# BlueESC.net
KiCad netlist of a schematic drawn in EAGLE
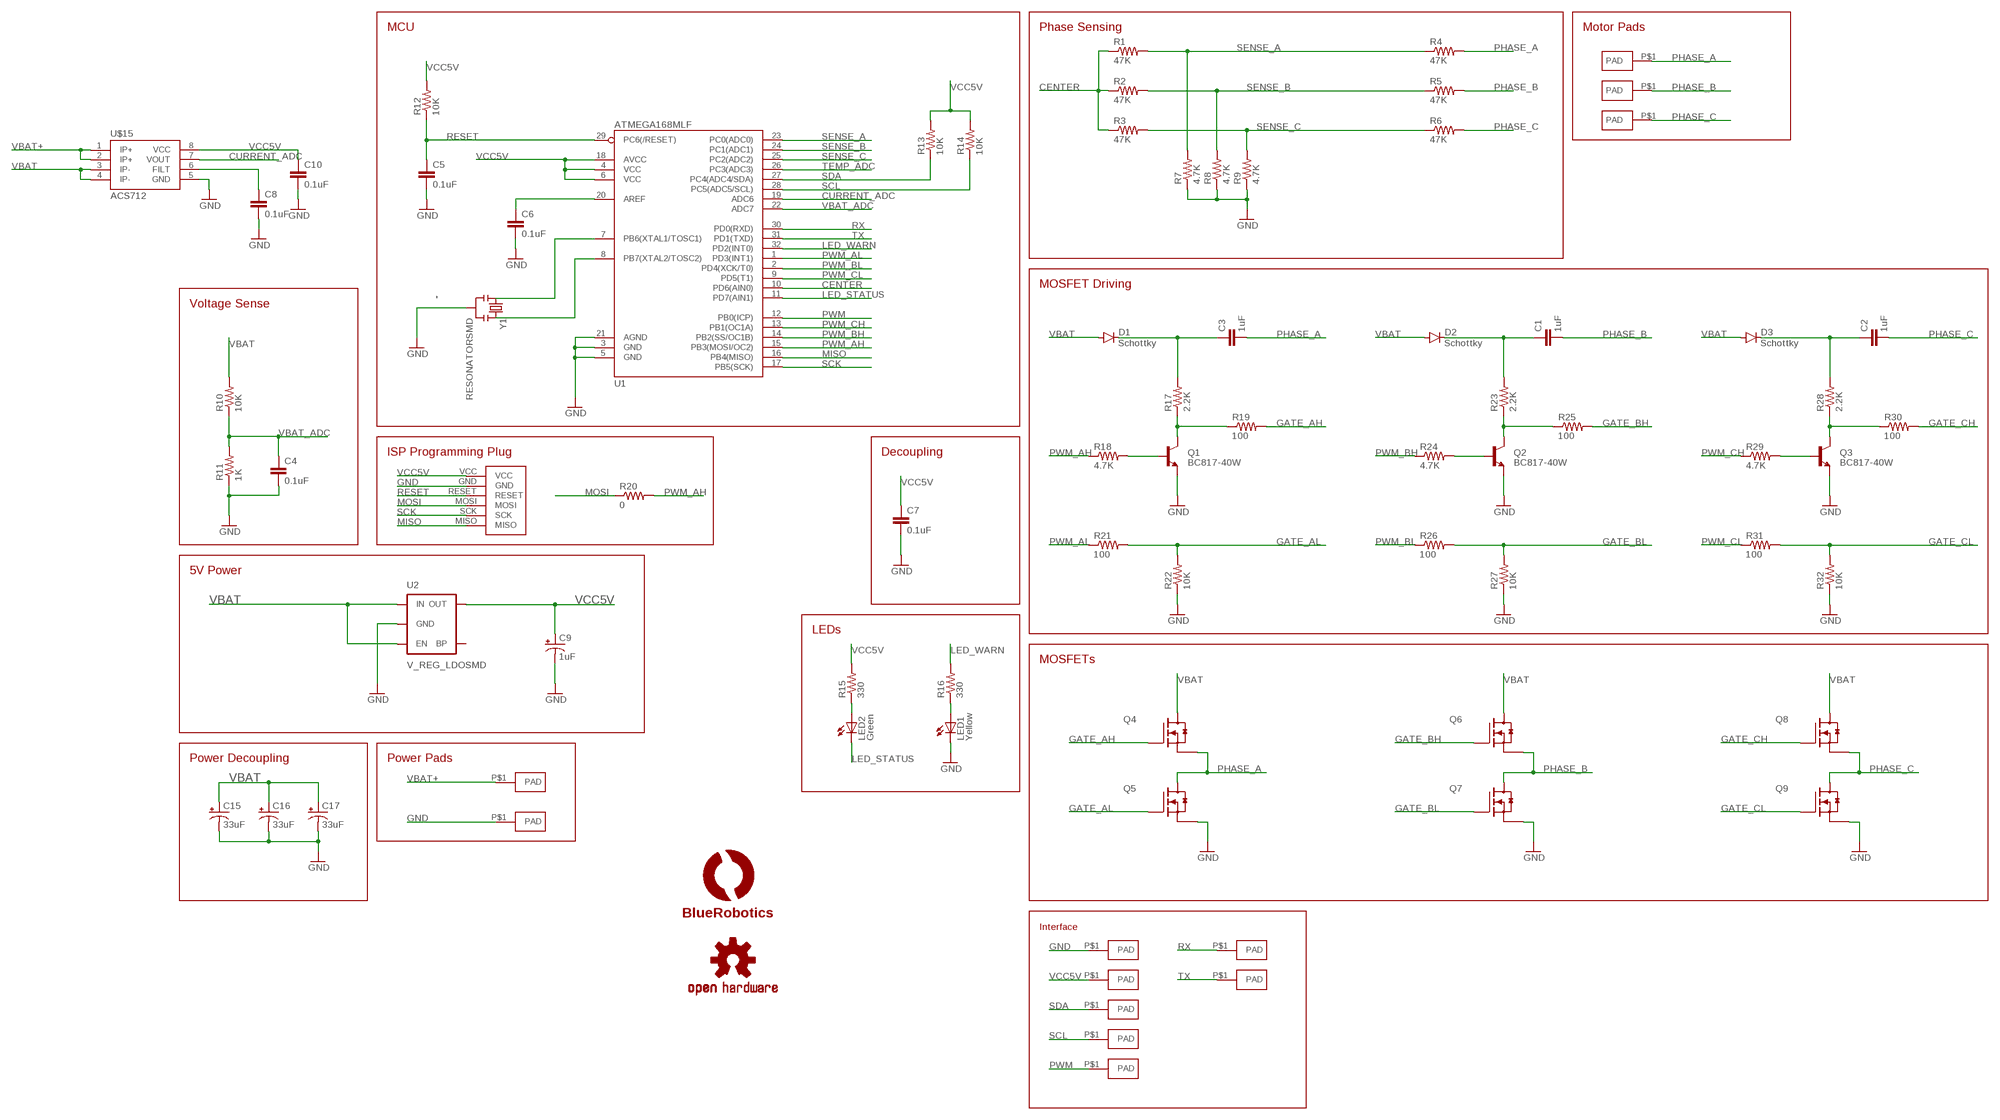
[diagram p0: schematic, sheet 1]

(export (version "E")
  (design (tool "Eeschema 10.0.6"))
  (components
    (comp (ref "C1")
      (value "1uF")
      (footprint "eagle-import:0805")
      (libsource (lib "eagle-import") (part "CAP0805"))
    )
    (comp (ref "C2")
      (value "1uF")
      (footprint "eagle-import:0805")
      (libsource (lib "eagle-import") (part "CAP0805"))
    )
    (comp (ref "C3")
      (value "1uF")
      (footprint "eagle-import:0805")
      (libsource (lib "eagle-import") (part "CAP0805"))
    )
    (comp (ref "C4")
      (value "0.1uF")
      (footprint "eagle-import:0603-CAP")
      (libsource (lib "eagle-import") (part "CAP0603-CAP"))
    )
    (comp (ref "C5")
      (value "0.1uF")
      (footprint "eagle-import:0603-CAP")
      (libsource (lib "eagle-import") (part "CAP0603-CAP"))
    )
    (comp (ref "C6")
      (value "0.1uF")
      (footprint "eagle-import:0603-CAP")
      (libsource (lib "eagle-import") (part "CAP0603-CAP"))
    )
    (comp (ref "C7")
      (value "0.1uF")
      (footprint "eagle-import:0603-CAP")
      (libsource (lib "eagle-import") (part "CAP0603-CAP"))
    )
    (comp (ref "C8")
      (value "0.1uF")
      (footprint "eagle-import:0603-CAP")
      (libsource (lib "eagle-import") (part "CAP0603-CAP"))
    )
    (comp (ref "C9")
      (value "1uF")
      (footprint "eagle-import:EIA3216")
      (libsource (lib "eagle-import") (part "CAP_POL1206"))
    )
    (comp (ref "C10")
      (value "0.1uF")
      (footprint "eagle-import:0603-CAP")
      (libsource (lib "eagle-import") (part "CAP0603-CAP"))
    )
    (comp (ref "C15")
      (value "33uF")
      (footprint "eagle-import:EIA6032")
      (libsource (lib "eagle-import") (part "CAP_POL6032"))
    )
    (comp (ref "C16")
      (value "33uF")
      (footprint "eagle-import:EIA6032")
      (libsource (lib "eagle-import") (part "CAP_POL6032"))
    )
    (comp (ref "C17")
      (value "33uF")
      (footprint "eagle-import:EIA6032")
      (libsource (lib "eagle-import") (part "CAP_POL6032"))
    )
    (comp (ref "D1")
      (value "Schottky")
      (footprint "eagle-import:SOD-323")
      (libsource (lib "eagle-import") (part "DIODESOD"))
    )
    (comp (ref "D2")
      (value "Schottky")
      (footprint "eagle-import:SOD-323")
      (libsource (lib "eagle-import") (part "DIODESOD"))
    )
    (comp (ref "D3")
      (value "Schottky")
      (footprint "eagle-import:SOD-323")
      (libsource (lib "eagle-import") (part "DIODESOD"))
    )
    (comp (ref "LED1")
      (value "Yellow")
      (footprint "eagle-import:LED3MM-NS")
      (libsource (lib "eagle-import") (part "LED-3MM-NO_SILK"))
    )
    (comp (ref "LED2")
      (value "Green")
      (footprint "eagle-import:LED3MM-NS")
      (libsource (lib "eagle-import") (part "LED-3MM-NO_SILK"))
    )
    (comp (ref "LOGO1")
      (value "OSHW-LOGOS")
      (footprint "eagle-import:OSHW-LOGO-S")
      (libsource (lib "eagle-import") (part "OSHW-LOGOS"))
    )
    (comp (ref "Q1")
      (value "BC817-40W")
      (footprint "eagle-import:SOT23")
      (libsource (lib "eagle-import") (part "TRANSISTOR_NPNSOT23"))
    )
    (comp (ref "Q2")
      (value "BC817-40W")
      (footprint "eagle-import:SOT23")
      (libsource (lib "eagle-import") (part "TRANSISTOR_NPNSOT23"))
    )
    (comp (ref "Q3")
      (value "BC817-40W")
      (footprint "eagle-import:SOT23")
      (libsource (lib "eagle-import") (part "TRANSISTOR_NPNSOT23"))
    )
    (comp (ref "Q4")
      (value "SI7370")
      (footprint "eagle-import:POWERPAK-SO-08")
      (libsource (lib "eagle-import") (part "SI7370"))
    )
    (comp (ref "Q5")
      (value "SI7370")
      (footprint "eagle-import:POWERPAK-SO-08")
      (libsource (lib "eagle-import") (part "SI7370"))
    )
    (comp (ref "Q6")
      (value "SI7370")
      (footprint "eagle-import:POWERPAK-SO-08")
      (libsource (lib "eagle-import") (part "SI7370"))
    )
    (comp (ref "Q7")
      (value "SI7370")
      (footprint "eagle-import:POWERPAK-SO-08")
      (libsource (lib "eagle-import") (part "SI7370"))
    )
    (comp (ref "Q8")
      (value "SI7370")
      (footprint "eagle-import:POWERPAK-SO-08")
      (libsource (lib "eagle-import") (part "SI7370"))
    )
    (comp (ref "Q9")
      (value "SI7370")
      (footprint "eagle-import:POWERPAK-SO-08")
      (libsource (lib "eagle-import") (part "SI7370"))
    )
    (comp (ref "R1")
      (value "47K")
      (footprint "eagle-import:0603-RES")
      (libsource (lib "eagle-import") (part "33KOHM1/10W1%(0603)"))
    )
    (comp (ref "R2")
      (value "47K")
      (footprint "eagle-import:0603-RES")
      (libsource (lib "eagle-import") (part "33KOHM1/10W1%(0603)"))
    )
    (comp (ref "R3")
      (value "47K")
      (footprint "eagle-import:0603-RES")
      (libsource (lib "eagle-import") (part "33KOHM1/10W1%(0603)"))
    )
    (comp (ref "R4")
      (value "47K")
      (footprint "eagle-import:0603-RES")
      (libsource (lib "eagle-import") (part "33KOHM1/10W1%(0603)"))
    )
    (comp (ref "R5")
      (value "47K")
      (footprint "eagle-import:0603-RES")
      (libsource (lib "eagle-import") (part "33KOHM1/10W1%(0603)"))
    )
    (comp (ref "R6")
      (value "47K")
      (footprint "eagle-import:0603-RES")
      (libsource (lib "eagle-import") (part "33KOHM1/10W1%(0603)"))
    )
    (comp (ref "R7")
      (value "4.7K")
      (footprint "eagle-import:0603-RES")
      (libsource (lib "eagle-import") (part "RESISTOR0603"))
    )
    (comp (ref "R8")
      (value "4.7K")
      (footprint "eagle-import:0603-RES")
      (libsource (lib "eagle-import") (part "RESISTOR0603"))
    )
    (comp (ref "R9")
      (value "4.7K")
      (footprint "eagle-import:0603-RES")
      (libsource (lib "eagle-import") (part "RESISTOR0603"))
    )
    (comp (ref "R10")
      (value "10K")
      (footprint "eagle-import:0603-RES")
      (libsource (lib "eagle-import") (part "33KOHM1/10W1%(0603)"))
    )
    (comp (ref "R11")
      (value "1K")
      (footprint "eagle-import:0603-RES")
      (libsource (lib "eagle-import") (part "33KOHM1/10W1%(0603)"))
    )
    (comp (ref "R12")
      (value "10K")
      (footprint "eagle-import:0603-RES")
      (libsource (lib "eagle-import") (part "33KOHM1/10W1%(0603)"))
    )
    (comp (ref "R13")
      (value "10K")
      (footprint "eagle-import:0603-RES")
      (libsource (lib "eagle-import") (part "33KOHM1/10W1%(0603)"))
    )
    (comp (ref "R14")
      (value "10K")
      (footprint "eagle-import:0603-RES")
      (libsource (lib "eagle-import") (part "33KOHM1/10W1%(0603)"))
    )
    (comp (ref "R15")
      (value "330")
      (footprint "eagle-import:0603-RES")
      (libsource (lib "eagle-import") (part "RESISTOR0603-RES"))
    )
    (comp (ref "R16")
      (value "330")
      (footprint "eagle-import:0603-RES")
      (libsource (lib "eagle-import") (part "RESISTOR0603-RES"))
    )
    (comp (ref "R17")
      (value "2.2K")
      (footprint "eagle-import:0603-RES")
      (libsource (lib "eagle-import") (part "33KOHM1/10W1%(0603)"))
    )
    (comp (ref "R18")
      (value "4.7K")
      (footprint "eagle-import:0603-RES")
      (libsource (lib "eagle-import") (part "33KOHM1/10W1%(0603)"))
    )
    (comp (ref "R19")
      (value "100")
      (footprint "eagle-import:0603-RES")
      (libsource (lib "eagle-import") (part "33KOHM1/10W1%(0603)"))
    )
    (comp (ref "R20")
      (value "0")
      (footprint "eagle-import:0603-RES")
      (libsource (lib "eagle-import") (part "33KOHM1/10W1%(0603)"))
    )
    (comp (ref "R21")
      (value "100")
      (footprint "eagle-import:0603-RES")
      (libsource (lib "eagle-import") (part "33KOHM1/10W1%(0603)"))
    )
    (comp (ref "R22")
      (value "10K")
      (footprint "eagle-import:0603-RES")
      (libsource (lib "eagle-import") (part "33KOHM1/10W1%(0603)"))
    )
    (comp (ref "R23")
      (value "2.2K")
      (footprint "eagle-import:0603-RES")
      (libsource (lib "eagle-import") (part "33KOHM1/10W1%(0603)"))
    )
    (comp (ref "R24")
      (value "4.7K")
      (footprint "eagle-import:0603-RES")
      (libsource (lib "eagle-import") (part "33KOHM1/10W1%(0603)"))
    )
    (comp (ref "R25")
      (value "100")
      (footprint "eagle-import:0603-RES")
      (libsource (lib "eagle-import") (part "33KOHM1/10W1%(0603)"))
    )
    (comp (ref "R26")
      (value "100")
      (footprint "eagle-import:0603-RES")
      (libsource (lib "eagle-import") (part "33KOHM1/10W1%(0603)"))
    )
    (comp (ref "R27")
      (value "10K")
      (footprint "eagle-import:0603-RES")
      (libsource (lib "eagle-import") (part "33KOHM1/10W1%(0603)"))
    )
    (comp (ref "R28")
      (value "2.2K")
      (footprint "eagle-import:0603-RES")
      (libsource (lib "eagle-import") (part "33KOHM1/10W1%(0603)"))
    )
    (comp (ref "R29")
      (value "4.7K")
      (footprint "eagle-import:0603-RES")
      (libsource (lib "eagle-import") (part "33KOHM1/10W1%(0603)"))
    )
    (comp (ref "R30")
      (value "100")
      (footprint "eagle-import:0603-RES")
      (libsource (lib "eagle-import") (part "33KOHM1/10W1%(0603)"))
    )
    (comp (ref "R31")
      (value "100")
      (footprint "eagle-import:0603-RES")
      (libsource (lib "eagle-import") (part "33KOHM1/10W1%(0603)"))
    )
    (comp (ref "R32")
      (value "10K")
      (footprint "eagle-import:0603-RES")
      (libsource (lib "eagle-import") (part "33KOHM1/10W1%(0603)"))
    )
    (comp (ref "U$1")
      (value "PAD2X3MM")
      (footprint "eagle-import:PAD-2X3MM")
      (libsource (lib "eagle-import") (part "PAD2X3MM"))
    )
    (comp (ref "U$2")
      (value "PAD2X3MM")
      (footprint "eagle-import:PAD-2X3MM")
      (libsource (lib "eagle-import") (part "PAD2X3MM"))
    )
    (comp (ref "U$3")
      (value "PAD1.5X3MM")
      (footprint "eagle-import:PAD-1.5X3MM")
      (libsource (lib "eagle-import") (part "PAD1.5X3MM"))
    )
    (comp (ref "U$4")
      (value "LOGOBR-LOGO-S")
      (footprint "eagle-import:BR-LOGO-SMALL")
      (libsource (lib "eagle-import") (part "LOGOBR-LOGO-S"))
    )
    (comp (ref "U$5")
      (value "PAD2X3MM")
      (footprint "eagle-import:PAD-2X3MM")
      (libsource (lib "eagle-import") (part "PAD2X3MM"))
    )
    (comp (ref "U$6")
      (value "PAD2X3MM")
      (footprint "eagle-import:PAD-2X3MM")
      (libsource (lib "eagle-import") (part "PAD2X3MM"))
    )
    (comp (ref "U$7")
      (value "PAD2X3MM")
      (footprint "eagle-import:PAD-2X3MM")
      (libsource (lib "eagle-import") (part "PAD2X3MM"))
    )
    (comp (ref "U$8")
      (value "PAD1.5X3MM")
      (footprint "eagle-import:PAD-1.5X3MM")
      (libsource (lib "eagle-import") (part "PAD1.5X3MM"))
    )
    (comp (ref "U$9")
      (value "PAD1.5X3MM")
      (footprint "eagle-import:PAD-1.5X3MM")
      (libsource (lib "eagle-import") (part "PAD1.5X3MM"))
    )
    (comp (ref "U$10")
      (value "PAD1.5X3MM")
      (footprint "eagle-import:PAD-1.5X3MM")
      (libsource (lib "eagle-import") (part "PAD1.5X3MM"))
    )
    (comp (ref "U$11")
      (value "PAD1.5X3MM")
      (footprint "eagle-import:PAD-1.5X3MM")
      (libsource (lib "eagle-import") (part "PAD1.5X3MM"))
    )
    (comp (ref "U$12")
      (value "PAD1.5X3MM")
      (footprint "eagle-import:PAD-1.5X3MM")
      (libsource (lib "eagle-import") (part "PAD1.5X3MM"))
    )
    (comp (ref "U$13")
      (value "PAD1.5X3MM")
      (footprint "eagle-import:PAD-1.5X3MM")
      (libsource (lib "eagle-import") (part "PAD1.5X3MM"))
    )
    (comp (ref "U$14")
      (value "AVR-ISPTINY-SMD")
      (footprint "eagle-import:AVR-ISP-TINY")
      (libsource (lib "eagle-import") (part "AVR-ISPTINY-SMD"))
    )
    (comp (ref "U$15")
      (value "ACS712")
      (footprint "eagle-import:SO08")
      (libsource (lib "eagle-import") (part "ACS712"))
    )
    (comp (ref "U1")
      (value "ATMEGA168MLF")
      (footprint "eagle-import:MLF32")
      (libsource (lib "eagle-import") (part "ATMEGA168MLF"))
    )
    (comp (ref "U2")
      (value "V_REG_LDOSMD")
      (footprint "eagle-import:SOT23-5")
      (libsource (lib "eagle-import") (part "V_REG_LDOSMD"))
    )
    (comp (ref "Y1")
      (value "RESONATORSMD")
      (footprint "eagle-import:RESONATOR-SMD")
      (libsource (lib "eagle-import") (part "RESONATORSMD"))
    )
  )
  (nets
    (net (code "1") (name "/CENTER") (class "Default")
      (node (ref "R1") (pin "1") (pinfunction "1_1") (pintype "passive"))
      (node (ref "R2") (pin "1") (pinfunction "1_1") (pintype "passive"))
      (node (ref "R3") (pin "1") (pinfunction "1_1") (pintype "passive"))
      (node (ref "U1") (pin "10") (pinfunction "PD6(AIN0)_10") (pintype "bidirectional"))
    )
    (net (code "2") (name "/CURRENT_ADC") (class "Default")
      (node (ref "U$15") (pin "7") (pinfunction "VOUT_7") (pintype "bidirectional"))
      (node (ref "U1") (pin "19") (pinfunction "ADC6_19") (pintype "bidirectional"))
    )
    (net (code "3") (name "/GATE_AH") (class "Default")
      (node (ref "Q4") (pin "4") (pinfunction "G_4") (pintype "passive"))
      (node (ref "R19") (pin "2") (pinfunction "2_2") (pintype "passive"))
    )
    (net (code "4") (name "/GATE_AL") (class "Default")
      (node (ref "Q5") (pin "4") (pinfunction "G_4") (pintype "passive"))
      (node (ref "R21") (pin "2") (pinfunction "2_2") (pintype "passive"))
      (node (ref "R22") (pin "2") (pinfunction "2_2") (pintype "passive"))
    )
    (net (code "5") (name "/GATE_BH") (class "Default")
      (node (ref "Q6") (pin "4") (pinfunction "G_4") (pintype "passive"))
      (node (ref "R25") (pin "2") (pinfunction "2_2") (pintype "passive"))
    )
    (net (code "6") (name "/GATE_BL") (class "Default")
      (node (ref "Q7") (pin "4") (pinfunction "G_4") (pintype "passive"))
      (node (ref "R26") (pin "2") (pinfunction "2_2") (pintype "passive"))
      (node (ref "R27") (pin "2") (pinfunction "2_2") (pintype "passive"))
    )
    (net (code "7") (name "/GATE_CH") (class "Default")
      (node (ref "Q8") (pin "4") (pinfunction "G_4") (pintype "passive"))
      (node (ref "R30") (pin "2") (pinfunction "2_2") (pintype "passive"))
    )
    (net (code "8") (name "/GATE_CL") (class "Default")
      (node (ref "Q9") (pin "4") (pinfunction "G_4") (pintype "passive"))
      (node (ref "R31") (pin "2") (pinfunction "2_2") (pintype "passive"))
      (node (ref "R32") (pin "2") (pinfunction "2_2") (pintype "passive"))
    )
    (net (code "9") (name "/LED_STATUS") (class "Default")
      (node (ref "LED2") (pin "K") (pinfunction "C_K") (pintype "passive"))
      (node (ref "U1") (pin "11") (pinfunction "PD7(AIN1)_11") (pintype "bidirectional"))
    )
    (net (code "10") (name "/LED_WARN") (class "Default")
      (node (ref "R16") (pin "2") (pinfunction "2_2") (pintype "passive"))
      (node (ref "U1") (pin "32") (pinfunction "PD2(INT0)_32") (pintype "bidirectional"))
    )
    (net (code "11") (name "/MISO") (class "Default")
      (node (ref "U$14") (pin "MISO") (pinfunction "MISO_MISO") (pintype "bidirectional"))
      (node (ref "U1") (pin "16") (pinfunction "PB4(MISO)_16") (pintype "bidirectional"))
    )
    (net (code "12") (name "/MOSI") (class "Default")
      (node (ref "R20") (pin "1") (pinfunction "1_1") (pintype "passive"))
      (node (ref "U$14") (pin "MOSI") (pinfunction "MOSI_MOSI") (pintype "bidirectional"))
    )
    (net (code "13") (name "/PHASE_A") (class "Default")
      (node (ref "C3") (pin "2") (pinfunction "2_2") (pintype "passive"))
      (node (ref "Q4") (pin "3") (pinfunction "S3_3") (pintype "passive"))
      (node (ref "Q5") (pin "5-8") (pinfunction "D_5-8") (pintype "passive"))
      (node (ref "R4") (pin "2") (pinfunction "2_2") (pintype "passive"))
      (node (ref "U$5") (pin "P$1") (pinfunction "PAD_P$1") (pintype "bidirectional"))
    )
    (net (code "14") (name "/PHASE_B") (class "Default")
      (node (ref "C1") (pin "2") (pinfunction "2_2") (pintype "passive"))
      (node (ref "Q6") (pin "3") (pinfunction "S3_3") (pintype "passive"))
      (node (ref "Q7") (pin "5-8") (pinfunction "D_5-8") (pintype "passive"))
      (node (ref "R5") (pin "2") (pinfunction "2_2") (pintype "passive"))
      (node (ref "U$6") (pin "P$1") (pinfunction "PAD_P$1") (pintype "bidirectional"))
    )
    (net (code "15") (name "/PHASE_C") (class "Default")
      (node (ref "C2") (pin "2") (pinfunction "2_2") (pintype "passive"))
      (node (ref "Q8") (pin "3") (pinfunction "S3_3") (pintype "passive"))
      (node (ref "Q9") (pin "5-8") (pinfunction "D_5-8") (pintype "passive"))
      (node (ref "R6") (pin "2") (pinfunction "2_2") (pintype "passive"))
      (node (ref "U$7") (pin "P$1") (pinfunction "PAD_P$1") (pintype "bidirectional"))
    )
    (net (code "16") (name "/PWM") (class "Default")
      (node (ref "U$11") (pin "P$1") (pinfunction "PAD_P$1") (pintype "bidirectional"))
      (node (ref "U1") (pin "12") (pinfunction "PB0(ICP)_12") (pintype "bidirectional"))
    )
    (net (code "17") (name "/PWM_AH") (class "Default")
      (node (ref "R18") (pin "1") (pinfunction "1_1") (pintype "passive"))
      (node (ref "R20") (pin "2") (pinfunction "2_2") (pintype "passive"))
      (node (ref "U1") (pin "15") (pinfunction "PB3(MOSI/OC2)_15") (pintype "bidirectional"))
    )
    (net (code "18") (name "/PWM_AL") (class "Default")
      (node (ref "R21") (pin "1") (pinfunction "1_1") (pintype "passive"))
      (node (ref "U1") (pin "1") (pinfunction "PD3(INT1)_1") (pintype "bidirectional"))
    )
    (net (code "19") (name "/PWM_BH") (class "Default")
      (node (ref "R24") (pin "1") (pinfunction "1_1") (pintype "passive"))
      (node (ref "U1") (pin "14") (pinfunction "PB2(SS/OC1B)_14") (pintype "bidirectional"))
    )
    (net (code "20") (name "/PWM_BL") (class "Default")
      (node (ref "R26") (pin "1") (pinfunction "1_1") (pintype "passive"))
      (node (ref "U1") (pin "2") (pinfunction "PD4(XCK/T0)_2") (pintype "bidirectional"))
    )
    (net (code "21") (name "/PWM_CH") (class "Default")
      (node (ref "R29") (pin "1") (pinfunction "1_1") (pintype "passive"))
      (node (ref "U1") (pin "13") (pinfunction "PB1(OC1A)_13") (pintype "bidirectional"))
    )
    (net (code "22") (name "/PWM_CL") (class "Default")
      (node (ref "R31") (pin "1") (pinfunction "1_1") (pintype "passive"))
      (node (ref "U1") (pin "9") (pinfunction "PD5(T1)_9") (pintype "bidirectional"))
    )
    (net (code "23") (name "/RESET") (class "Default")
      (node (ref "C5") (pin "1") (pinfunction "1_1") (pintype "passive"))
      (node (ref "R12") (pin "1") (pinfunction "1_1") (pintype "passive"))
      (node (ref "U$14") (pin "RESET") (pinfunction "RESET_RESET") (pintype "bidirectional"))
      (node (ref "U1") (pin "29") (pinfunction "PC6(/RESET)_29") (pintype "bidirectional"))
    )
    (net (code "24") (name "/RX") (class "Default")
      (node (ref "U$12") (pin "P$1") (pinfunction "PAD_P$1") (pintype "bidirectional"))
      (node (ref "U1") (pin "30") (pinfunction "PD0(RXD)_30") (pintype "bidirectional"))
    )
    (net (code "25") (name "/SCK") (class "Default")
      (node (ref "U$14") (pin "SCK") (pinfunction "SCK_SCK") (pintype "bidirectional"))
      (node (ref "U1") (pin "17") (pinfunction "PB5(SCK)_17") (pintype "bidirectional"))
    )
    (net (code "26") (name "/SCL") (class "Default")
      (node (ref "R14") (pin "1") (pinfunction "1_1") (pintype "passive"))
      (node (ref "U$10") (pin "P$1") (pinfunction "PAD_P$1") (pintype "bidirectional"))
      (node (ref "U1") (pin "28") (pinfunction "PC5(ADC5/SCL)_28") (pintype "bidirectional"))
    )
    (net (code "27") (name "/SDA") (class "Default")
      (node (ref "R13") (pin "1") (pinfunction "1_1") (pintype "passive"))
      (node (ref "U$9") (pin "P$1") (pinfunction "PAD_P$1") (pintype "bidirectional"))
      (node (ref "U1") (pin "27") (pinfunction "PC4(ADC4/SDA)_27") (pintype "bidirectional"))
    )
    (net (code "28") (name "/SENSE_A") (class "Default")
      (node (ref "R1") (pin "2") (pinfunction "2_2") (pintype "passive"))
      (node (ref "R4") (pin "1") (pinfunction "1_1") (pintype "passive"))
      (node (ref "R7") (pin "2") (pinfunction "2_2") (pintype "passive"))
      (node (ref "U1") (pin "23") (pinfunction "PC0(ADC0)_23") (pintype "bidirectional"))
    )
    (net (code "29") (name "/SENSE_B") (class "Default")
      (node (ref "R2") (pin "2") (pinfunction "2_2") (pintype "passive"))
      (node (ref "R5") (pin "1") (pinfunction "1_1") (pintype "passive"))
      (node (ref "R8") (pin "2") (pinfunction "2_2") (pintype "passive"))
      (node (ref "U1") (pin "24") (pinfunction "PC1(ADC1)_24") (pintype "bidirectional"))
    )
    (net (code "30") (name "/SENSE_C") (class "Default")
      (node (ref "R3") (pin "2") (pinfunction "2_2") (pintype "passive"))
      (node (ref "R6") (pin "1") (pinfunction "1_1") (pintype "passive"))
      (node (ref "R9") (pin "2") (pinfunction "2_2") (pintype "passive"))
      (node (ref "U1") (pin "25") (pinfunction "PC2(ADC2)_25") (pintype "bidirectional"))
    )
    (net (code "31") (name "/TEMP_ADC") (class "Default")
      (node (ref "U1") (pin "26") (pinfunction "PC3(ADC3)_26") (pintype "bidirectional"))
    )
    (net (code "32") (name "/TX") (class "Default")
      (node (ref "U$13") (pin "P$1") (pinfunction "PAD_P$1") (pintype "bidirectional"))
      (node (ref "U1") (pin "31") (pinfunction "PD1(TXD)_31") (pintype "bidirectional"))
    )
    (net (code "33") (name "/VBAT") (class "Default")
      (node (ref "C15") (pin "P$1") (pinfunction "+_P$1") (pintype "passive"))
      (node (ref "C16") (pin "P$1") (pinfunction "+_P$1") (pintype "passive"))
      (node (ref "C17") (pin "P$1") (pinfunction "+_P$1") (pintype "passive"))
      (node (ref "D1") (pin "A") (pinfunction "A_A") (pintype "passive"))
      (node (ref "D2") (pin "A") (pinfunction "A_A") (pintype "passive"))
      (node (ref "D3") (pin "A") (pinfunction "A_A") (pintype "passive"))
      (node (ref "Q4") (pin "5-8") (pinfunction "D_5-8") (pintype "passive"))
      (node (ref "Q6") (pin "5-8") (pinfunction "D_5-8") (pintype "passive"))
      (node (ref "Q8") (pin "5-8") (pinfunction "D_5-8") (pintype "passive"))
      (node (ref "R10") (pin "2") (pinfunction "2_2") (pintype "passive"))
      (node (ref "U$15") (pin "3") (pinfunction "IP-_3") (pintype "bidirectional"))
      (node (ref "U$15") (pin "4") (pinfunction "IP-_4") (pintype "bidirectional"))
      (node (ref "U2") (pin "1") (pinfunction "IN_1") (pintype "input"))
      (node (ref "U2") (pin "3") (pinfunction "EN_3") (pintype "input"))
    )
    (net (code "34") (name "/VBAT+") (class "Default")
      (node (ref "U$1") (pin "P$1") (pinfunction "PAD_P$1") (pintype "bidirectional"))
      (node (ref "U$15") (pin "1") (pinfunction "IP+_1") (pintype "bidirectional"))
      (node (ref "U$15") (pin "2") (pinfunction "IP+_2") (pintype "bidirectional"))
    )
    (net (code "35") (name "/VBAT_ADC") (class "Default")
      (node (ref "C4") (pin "1") (pinfunction "1_1") (pintype "passive"))
      (node (ref "R10") (pin "1") (pinfunction "1_1") (pintype "passive"))
      (node (ref "R11") (pin "2") (pinfunction "2_2") (pintype "passive"))
      (node (ref "U1") (pin "22") (pinfunction "ADC7_22") (pintype "bidirectional"))
    )
    (net (code "36") (name "/VCC5V") (class "Default")
      (node (ref "C10") (pin "1") (pinfunction "1_1") (pintype "passive"))
      (node (ref "C7") (pin "1") (pinfunction "1_1") (pintype "passive"))
      (node (ref "C9") (pin "A") (pinfunction "+_A") (pintype "passive"))
      (node (ref "R12") (pin "2") (pinfunction "2_2") (pintype "passive"))
      (node (ref "R13") (pin "2") (pinfunction "2_2") (pintype "passive"))
      (node (ref "R14") (pin "2") (pinfunction "2_2") (pintype "passive"))
      (node (ref "R15") (pin "2") (pinfunction "2_2") (pintype "passive"))
      (node (ref "U$14") (pin "VCC") (pinfunction "VCC_VCC") (pintype "power_in"))
      (node (ref "U$15") (pin "8") (pinfunction "VCC_8") (pintype "bidirectional"))
      (node (ref "U$8") (pin "P$1") (pinfunction "PAD_P$1") (pintype "bidirectional"))
      (node (ref "U1") (pin "18") (pinfunction "AVCC_18") (pintype "bidirectional"))
      (node (ref "U1") (pin "4") (pinfunction "VCC_4") (pintype "bidirectional"))
      (node (ref "U1") (pin "6") (pinfunction "VCC_6") (pintype "bidirectional"))
      (node (ref "U2") (pin "5") (pinfunction "OUT_5") (pintype "passive"))
    )
    (net (code "37") (name "GND") (class "Default")
      (node (ref "C10") (pin "2") (pinfunction "2_2") (pintype "passive"))
      (node (ref "C15") (pin "P$2") (pinfunction "-_P$2") (pintype "passive"))
      (node (ref "C16") (pin "P$2") (pinfunction "-_P$2") (pintype "passive"))
      (node (ref "C17") (pin "P$2") (pinfunction "-_P$2") (pintype "passive"))
      (node (ref "C4") (pin "2") (pinfunction "2_2") (pintype "passive"))
      (node (ref "C5") (pin "2") (pinfunction "2_2") (pintype "passive"))
      (node (ref "C6") (pin "2") (pinfunction "2_2") (pintype "passive"))
      (node (ref "C7") (pin "2") (pinfunction "2_2") (pintype "passive"))
      (node (ref "C8") (pin "2") (pinfunction "2_2") (pintype "passive"))
      (node (ref "C9") (pin "C") (pinfunction "-_C") (pintype "passive"))
      (node (ref "LED1") (pin "K") (pinfunction "C_K") (pintype "passive"))
      (node (ref "Q1") (pin "2") (pinfunction "E_2") (pintype "passive"))
      (node (ref "Q2") (pin "2") (pinfunction "E_2") (pintype "passive"))
      (node (ref "Q3") (pin "2") (pinfunction "E_2") (pintype "passive"))
      (node (ref "Q5") (pin "3") (pinfunction "S3_3") (pintype "passive"))
      (node (ref "Q7") (pin "3") (pinfunction "S3_3") (pintype "passive"))
      (node (ref "Q9") (pin "3") (pinfunction "S3_3") (pintype "passive"))
      (node (ref "R11") (pin "1") (pinfunction "1_1") (pintype "passive"))
      (node (ref "R22") (pin "1") (pinfunction "1_1") (pintype "passive"))
      (node (ref "R27") (pin "1") (pinfunction "1_1") (pintype "passive"))
      (node (ref "R32") (pin "1") (pinfunction "1_1") (pintype "passive"))
      (node (ref "R7") (pin "1") (pinfunction "1_1") (pintype "passive"))
      (node (ref "R8") (pin "1") (pinfunction "1_1") (pintype "passive"))
      (node (ref "R9") (pin "1") (pinfunction "1_1") (pintype "passive"))
      (node (ref "U$14") (pin "GND") (pinfunction "GND_GND") (pintype "power_in"))
      (node (ref "U$15") (pin "5") (pinfunction "GND_5") (pintype "bidirectional"))
      (node (ref "U$2") (pin "P$1") (pinfunction "PAD_P$1") (pintype "bidirectional"))
      (node (ref "U$3") (pin "P$1") (pinfunction "PAD_P$1") (pintype "bidirectional"))
      (node (ref "U1") (pin "21") (pinfunction "AGND_21") (pintype "bidirectional"))
      (node (ref "U1") (pin "3") (pinfunction "GND_3") (pintype "bidirectional"))
      (node (ref "U1") (pin "5") (pinfunction "GND_5") (pintype "bidirectional"))
      (node (ref "U2") (pin "2") (pinfunction "GND_2") (pintype "input"))
      (node (ref "Y1") (pin "2") (pinfunction "2_2") (pintype "passive"))
    )
    (net (code "38") (name "Net-(C1-Pad1)") (class "Default")
      (node (ref "C1") (pin "1") (pinfunction "1_1") (pintype "passive"))
      (node (ref "D2") (pin "C") (pinfunction "C_C") (pintype "passive"))
      (node (ref "R23") (pin "2") (pinfunction "2_2") (pintype "passive"))
    )
    (net (code "39") (name "Net-(C2-Pad1)") (class "Default")
      (node (ref "C2") (pin "1") (pinfunction "1_1") (pintype "passive"))
      (node (ref "D3") (pin "C") (pinfunction "C_C") (pintype "passive"))
      (node (ref "R28") (pin "2") (pinfunction "2_2") (pintype "passive"))
    )
    (net (code "40") (name "Net-(C3-Pad1)") (class "Default")
      (node (ref "C3") (pin "1") (pinfunction "1_1") (pintype "passive"))
      (node (ref "D1") (pin "C") (pinfunction "C_C") (pintype "passive"))
      (node (ref "R17") (pin "2") (pinfunction "2_2") (pintype "passive"))
    )
    (net (code "41") (name "Net-(LED1-PadA)") (class "Default")
      (node (ref "LED1") (pin "A") (pinfunction "A_A") (pintype "passive"))
      (node (ref "R16") (pin "1") (pinfunction "1_1") (pintype "passive"))
    )
    (net (code "42") (name "Net-(LED2-PadA)") (class "Default")
      (node (ref "LED2") (pin "A") (pinfunction "A_A") (pintype "passive"))
      (node (ref "R15") (pin "1") (pinfunction "1_1") (pintype "passive"))
    )
    (net (code "43") (name "Net-(Q1-B)") (class "Default")
      (node (ref "Q1") (pin "1") (pinfunction "B_1") (pintype "passive"))
      (node (ref "R18") (pin "2") (pinfunction "2_2") (pintype "passive"))
    )
    (net (code "44") (name "Net-(Q1-C)") (class "Default")
      (node (ref "Q1") (pin "3") (pinfunction "C_3") (pintype "passive"))
      (node (ref "R17") (pin "1") (pinfunction "1_1") (pintype "passive"))
      (node (ref "R19") (pin "1") (pinfunction "1_1") (pintype "passive"))
    )
    (net (code "45") (name "Net-(Q2-B)") (class "Default")
      (node (ref "Q2") (pin "1") (pinfunction "B_1") (pintype "passive"))
      (node (ref "R24") (pin "2") (pinfunction "2_2") (pintype "passive"))
    )
    (net (code "46") (name "Net-(Q2-C)") (class "Default")
      (node (ref "Q2") (pin "3") (pinfunction "C_3") (pintype "passive"))
      (node (ref "R23") (pin "1") (pinfunction "1_1") (pintype "passive"))
      (node (ref "R25") (pin "1") (pinfunction "1_1") (pintype "passive"))
    )
    (net (code "47") (name "Net-(Q3-B)") (class "Default")
      (node (ref "Q3") (pin "1") (pinfunction "B_1") (pintype "passive"))
      (node (ref "R29") (pin "2") (pinfunction "2_2") (pintype "passive"))
    )
    (net (code "48") (name "Net-(Q3-C)") (class "Default")
      (node (ref "Q3") (pin "3") (pinfunction "C_3") (pintype "passive"))
      (node (ref "R28") (pin "1") (pinfunction "1_1") (pintype "passive"))
      (node (ref "R30") (pin "1") (pinfunction "1_1") (pintype "passive"))
    )
    (net (code "49") (name "Net-(U$15-FILT)") (class "Default")
      (node (ref "C8") (pin "1") (pinfunction "1_1") (pintype "passive"))
      (node (ref "U$15") (pin "6") (pinfunction "FILT_6") (pintype "bidirectional"))
    )
    (net (code "50") (name "Net-(U1-AREF)") (class "Default")
      (node (ref "C6") (pin "1") (pinfunction "1_1") (pintype "passive"))
      (node (ref "U1") (pin "20") (pinfunction "AREF_20") (pintype "bidirectional"))
    )
    (net (code "51") (name "Net-(U1-PB6(XTAL1{slash}TOSC1))") (class "Default")
      (node (ref "U1") (pin "7") (pinfunction "PB6(XTAL1/TOSC1)_7") (pintype "bidirectional"))
      (node (ref "Y1") (pin "1") (pinfunction "1_1") (pintype "passive"))
    )
    (net (code "52") (name "Net-(U1-PB7(XTAL2{slash}TOSC2))") (class "Default")
      (node (ref "U1") (pin "8") (pinfunction "PB7(XTAL2/TOSC2)_8") (pintype "bidirectional"))
      (node (ref "Y1") (pin "3") (pinfunction "3_3") (pintype "passive"))
    )
    (net (code "53") (name "unconnected-(Q4-S1-Pad1)") (class "Default")
      (node (ref "Q4") (pin "1") (pinfunction "S1_1") (pintype "passive"))
    )
    (net (code "54") (name "unconnected-(Q4-S2-Pad2)") (class "Default")
      (node (ref "Q4") (pin "2") (pinfunction "S2_2") (pintype "passive"))
    )
    (net (code "55") (name "unconnected-(Q5-S1-Pad1)") (class "Default")
      (node (ref "Q5") (pin "1") (pinfunction "S1_1") (pintype "passive"))
    )
    (net (code "56") (name "unconnected-(Q5-S2-Pad2)") (class "Default")
      (node (ref "Q5") (pin "2") (pinfunction "S2_2") (pintype "passive"))
    )
    (net (code "57") (name "unconnected-(Q6-S1-Pad1)") (class "Default")
      (node (ref "Q6") (pin "1") (pinfunction "S1_1") (pintype "passive"))
    )
    (net (code "58") (name "unconnected-(Q6-S2-Pad2)") (class "Default")
      (node (ref "Q6") (pin "2") (pinfunction "S2_2") (pintype "passive"))
    )
    (net (code "59") (name "unconnected-(Q7-S1-Pad1)") (class "Default")
      (node (ref "Q7") (pin "1") (pinfunction "S1_1") (pintype "passive"))
    )
    (net (code "60") (name "unconnected-(Q7-S2-Pad2)") (class "Default")
      (node (ref "Q7") (pin "2") (pinfunction "S2_2") (pintype "passive"))
    )
    (net (code "61") (name "unconnected-(Q8-S1-Pad1)") (class "Default")
      (node (ref "Q8") (pin "1") (pinfunction "S1_1") (pintype "passive"))
    )
    (net (code "62") (name "unconnected-(Q8-S2-Pad2)") (class "Default")
      (node (ref "Q8") (pin "2") (pinfunction "S2_2") (pintype "passive"))
    )
    (net (code "63") (name "unconnected-(Q9-S1-Pad1)") (class "Default")
      (node (ref "Q9") (pin "1") (pinfunction "S1_1") (pintype "passive"))
    )
    (net (code "64") (name "unconnected-(Q9-S2-Pad2)") (class "Default")
      (node (ref "Q9") (pin "2") (pinfunction "S2_2") (pintype "passive"))
    )
    (net (code "65") (name "unconnected-(U2-BP-Pad4)") (class "Default")
      (node (ref "U2") (pin "4") (pinfunction "BP_4") (pintype "input"))
    )
  )
)
